# STB_SensorBoard.net
KiCad netlist of a schematic drawn in Altium Designer
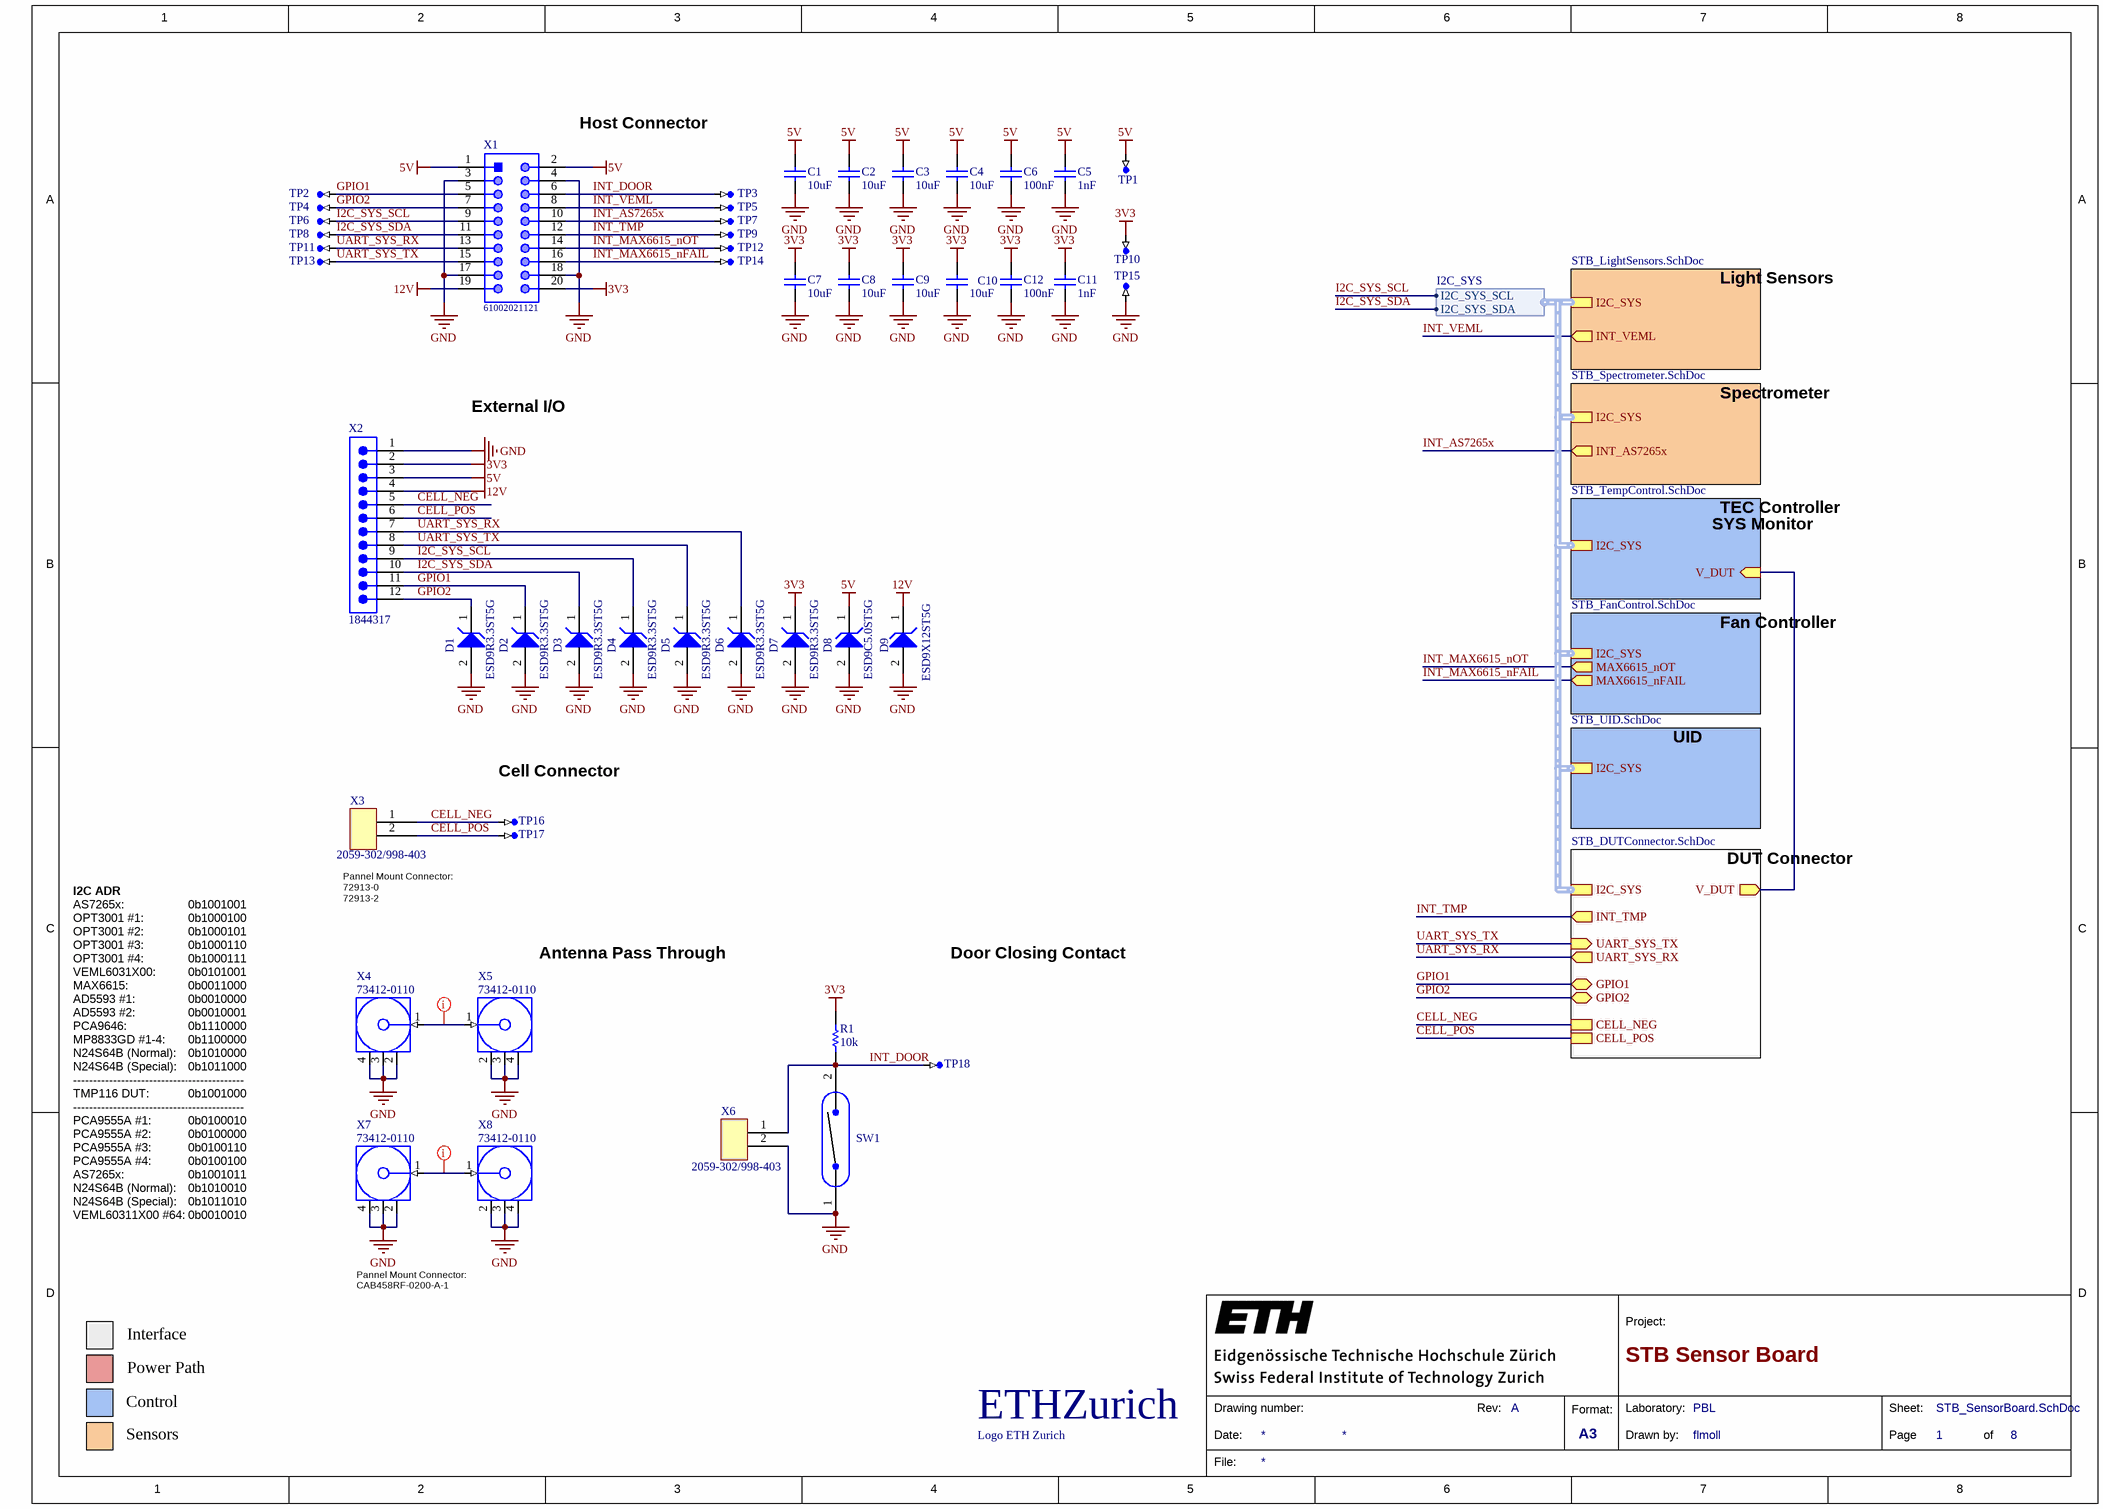
[diagram p0: STB_SensorBoard.SchDoc]

(export (version "E")
  (design (tool "Eeschema 10.0.6"))
  (components
    (comp (ref "A1")
      (value "Logo ETH Zurich")
      (footprint "eth-zurich_5mm")
      (libsource (lib "ETHZ Vault") (part "Logo ETH Zurich"))
    )
    (comp (ref "C1")
      (value "10uF")
      (footprint "CAPC0603(1608)100_L")
      (description "CAP 10uF 10V ±10% 0603 (1608 Metric) Thickness 1mm SMD")
      (fields (field (name "TOLERANCE") "Â±10%") (field (name "MANUFACTURER") "Samsung"))
      (libsource (lib "Altium Content Vault") (part "CMP-1035-02799-1"))
    )
    (comp (ref "C2")
      (value "10uF")
      (footprint "CAPC0603(1608)100_L")
      (description "CAP 10uF 10V ±10% 0603 (1608 Metric) Thickness 1mm SMD")
      (fields (field (name "TOLERANCE") "Â±10%") (field (name "MANUFACTURER") "Samsung"))
      (libsource (lib "Altium Content Vault") (part "CMP-1035-02799-1"))
    )
    (comp (ref "C3")
      (value "10uF")
      (footprint "CAPC0603(1608)100_L")
      (description "CAP 10uF 10V ±10% 0603 (1608 Metric) Thickness 1mm SMD")
      (fields (field (name "TOLERANCE") "Â±10%") (field (name "MANUFACTURER") "Samsung"))
      (libsource (lib "Altium Content Vault") (part "CMP-1035-02799-1"))
    )
    (comp (ref "C4")
      (value "10uF")
      (footprint "CAPC0603(1608)100_L")
      (description "CAP 10uF 10V ±10% 0603 (1608 Metric) Thickness 1mm SMD")
      (fields (field (name "TOLERANCE") "Â±10%") (field (name "MANUFACTURER") "Samsung"))
      (libsource (lib "Altium Content Vault") (part "CMP-1035-02799-1"))
    )
    (comp (ref "C5")
      (value "1nF")
      (footprint "CAPC1005X55X25ML5T10")
      (description "Chip Capacitor, 1 nF, +/- 10%, 50 V, -55 to 125 degC, 0402 (1005 Metric), RoHS, Tape and Reel")
      (fields (field (name "TOLERANCE") "10%") (field (name "MANUFACTURER") "Murata"))
      (libsource (lib "") (part "CAP-NP-2_1"))
    )
    (comp (ref "C6")
      (value "100nF")
      (footprint "CAPC1050X55X23LL05T13")
      (description "Chip Capacitor, 100 nF, +/- 10%, 16 V, -55 to 125 degC, 0402 (1005 Metric), RoHS, Tape and Reel")
      (fields
        (field (name "MANUFACTURER") "Samsung Electro-Mechanics")
        (field (name "MANUFACTURER PART NUMBER") "CL05B104KO5NNNC")
      )
      (libsource (lib "Altium Content Vault") (part "CAP-NP-2"))
    )
    (comp (ref "C7")
      (value "10uF")
      (footprint "CAPC0603(1608)100_L")
      (description "CAP 10uF 10V ±10% 0603 (1608 Metric) Thickness 1mm SMD")
      (fields (field (name "TOLERANCE") "Â±10%") (field (name "MANUFACTURER") "Samsung"))
      (libsource (lib "Altium Content Vault") (part "CMP-1035-02799-1"))
    )
    (comp (ref "C8")
      (value "10uF")
      (footprint "CAPC0603(1608)100_L")
      (description "CAP 10uF 10V ±10% 0603 (1608 Metric) Thickness 1mm SMD")
      (fields (field (name "TOLERANCE") "Â±10%") (field (name "MANUFACTURER") "Samsung"))
      (libsource (lib "Altium Content Vault") (part "CMP-1035-02799-1"))
    )
    (comp (ref "C9")
      (value "10uF")
      (footprint "CAPC0603(1608)100_L")
      (description "CAP 10uF 10V ±10% 0603 (1608 Metric) Thickness 1mm SMD")
      (fields (field (name "TOLERANCE") "Â±10%") (field (name "MANUFACTURER") "Samsung"))
      (libsource (lib "Altium Content Vault") (part "CMP-1035-02799-1"))
    )
    (comp (ref "C10")
      (value "10uF")
      (footprint "CAPC0603(1608)100_L")
      (description "CAP 10uF 10V ±10% 0603 (1608 Metric) Thickness 1mm SMD")
      (fields (field (name "TOLERANCE") "Â±10%") (field (name "MANUFACTURER") "Samsung"))
      (libsource (lib "Altium Content Vault") (part "CMP-1035-02799-1"))
    )
    (comp (ref "C11")
      (value "1nF")
      (footprint "CAPC1005X55X25ML5T10")
      (description "Chip Capacitor, 1 nF, +/- 10%, 50 V, -55 to 125 degC, 0402 (1005 Metric), RoHS, Tape and Reel")
      (fields (field (name "TOLERANCE") "10%") (field (name "MANUFACTURER") "Murata"))
      (libsource (lib "") (part "CAP-NP-2_1"))
    )
    (comp (ref "C12")
      (value "100nF")
      (footprint "CAPC1050X55X23LL05T13")
      (description "Chip Capacitor, 100 nF, +/- 10%, 16 V, -55 to 125 degC, 0402 (1005 Metric), RoHS, Tape and Reel")
      (fields
        (field (name "MANUFACTURER") "Samsung Electro-Mechanics")
        (field (name "MANUFACTURER PART NUMBER") "CL05B104KO5NNNC")
      )
      (libsource (lib "Altium Content Vault") (part "CAP-NP-2"))
    )
    (comp (ref "D1")
      (value "ESD9R3.3ST5G")
      (footprint "ONSC-SOD-923-2-514AB-01_V")
      (fields
        (field (name "MANUFACTURER") "On Semiconductor")
        (field (name "MANUFACTURER PART NUMBER") "SZESD9R3.3ST5G")
      )
      (libsource (lib "Altium Content Vault") (part "ONSC-K1A2-2_A"))
    )
    (comp (ref "D2")
      (value "ESD9R3.3ST5G")
      (footprint "ONSC-SOD-923-2-514AB-01_V")
      (fields
        (field (name "MANUFACTURER") "On Semiconductor")
        (field (name "MANUFACTURER PART NUMBER") "SZESD9R3.3ST5G")
      )
      (libsource (lib "Altium Content Vault") (part "ONSC-K1A2-2_A"))
    )
    (comp (ref "D3")
      (value "ESD9R3.3ST5G")
      (footprint "ONSC-SOD-923-2-514AB-01_V")
      (fields
        (field (name "MANUFACTURER") "On Semiconductor")
        (field (name "MANUFACTURER PART NUMBER") "SZESD9R3.3ST5G")
      )
      (libsource (lib "Altium Content Vault") (part "ONSC-K1A2-2_A"))
    )
    (comp (ref "D4")
      (value "ESD9R3.3ST5G")
      (footprint "ONSC-SOD-923-2-514AB-01_V")
      (fields
        (field (name "MANUFACTURER") "On Semiconductor")
        (field (name "MANUFACTURER PART NUMBER") "SZESD9R3.3ST5G")
      )
      (libsource (lib "Altium Content Vault") (part "ONSC-K1A2-2_A"))
    )
    (comp (ref "D5")
      (value "ESD9R3.3ST5G")
      (footprint "ONSC-SOD-923-2-514AB-01_V")
      (fields
        (field (name "MANUFACTURER") "On Semiconductor")
        (field (name "MANUFACTURER PART NUMBER") "SZESD9R3.3ST5G")
      )
      (libsource (lib "Altium Content Vault") (part "ONSC-K1A2-2_A"))
    )
    (comp (ref "D6")
      (value "ESD9R3.3ST5G")
      (footprint "ONSC-SOD-923-2-514AB-01_V")
      (fields
        (field (name "MANUFACTURER") "On Semiconductor")
        (field (name "MANUFACTURER PART NUMBER") "SZESD9R3.3ST5G")
      )
      (libsource (lib "Altium Content Vault") (part "ONSC-K1A2-2_A"))
    )
    (comp (ref "D7")
      (value "ESD9R3.3ST5G")
      (footprint "ONSC-SOD-923-2-514AB-01_V")
      (fields
        (field (name "MANUFACTURER") "On Semiconductor")
        (field (name "MANUFACTURER PART NUMBER") "SZESD9R3.3ST5G")
      )
      (libsource (lib "Altium Content Vault") (part "ONSC-K1A2-2_A"))
    )
    (comp (ref "D8")
      (value "ESD9C5.0ST5G")
      (footprint "ONSC-SOD-923-2-514AB-01_V")
      (fields (field (name "MANUFACTURER") "On Semiconductor"))
      (libsource (lib "Altium Content Vault") (part "ONSC-K1A2-2"))
    )
    (comp (ref "D9")
      (value "ESD9X12ST5G")
      (footprint "ONSC-SOD-923-2-514AA-01_V")
      (fields (field (name "MANUFACTURER") "On Semiconductor"))
      (libsource (lib "Altium Content Vault") (part "ONSC-K1A2-2"))
    )
    (comp (ref "R1")
      (value "10k")
      (footprint "RESC1005X40X25LL05T05")
      (description "Chip Resistor, 10 KOhm, +/- 1%, 0.1 W, -55 to 155 degC, 0402 (1005 Metric), RoHS, Tape and Reel")
      (fields (field (name "TOLERANCE") "1%") (field (name "MANUFACTURER") "Panasonic"))
      (libsource (lib "Altium Content Vault") (part "RES-2"))
    )
    (comp (ref "SW1")
      (value "MK17-B-2")
      (footprint "SMEL-MK17-B-2_V")
      (description "Molded Body Reed Switch, 100 V, 10 W, -40 to 130 degC, 2-Pin SMD, RoHS, Tape and Reel")
      (fields (field (name "MANUFACTURER") "Standex Meder"))
      (libsource (lib "Altium Content Vault") (part "SW-REED-2"))
    )
    (comp (ref "TP1")
      (value "testPoint_1mm")
      (footprint "TP-SM-C-100")
      (description "testPoint 1mm")
      (libsource (lib "STB_Schlib") (part "testPoint_1mm"))
    )
    (comp (ref "TP2")
      (value "testPoint_1mm")
      (footprint "TP-SM-C-100")
      (description "testPoint 1mm")
      (libsource (lib "STB_Schlib") (part "testPoint_1mm"))
    )
    (comp (ref "TP3")
      (value "testPoint_1mm")
      (footprint "TP-SM-C-100")
      (description "testPoint 1mm")
      (libsource (lib "STB_Schlib") (part "testPoint_1mm"))
    )
    (comp (ref "TP4")
      (value "testPoint_1mm")
      (footprint "TP-SM-C-100")
      (description "testPoint 1mm")
      (libsource (lib "STB_Schlib") (part "testPoint_1mm"))
    )
    (comp (ref "TP5")
      (value "testPoint_1mm")
      (footprint "TP-SM-C-100")
      (description "testPoint 1mm")
      (libsource (lib "STB_Schlib") (part "testPoint_1mm"))
    )
    (comp (ref "TP6")
      (value "testPoint_1mm")
      (footprint "TP-SM-C-100")
      (description "testPoint 1mm")
      (libsource (lib "STB_Schlib") (part "testPoint_1mm"))
    )
    (comp (ref "TP7")
      (value "testPoint_1mm")
      (footprint "TP-SM-C-100")
      (description "testPoint 1mm")
      (libsource (lib "STB_Schlib") (part "testPoint_1mm"))
    )
    (comp (ref "TP8")
      (value "testPoint_1mm")
      (footprint "TP-SM-C-100")
      (description "testPoint 1mm")
      (libsource (lib "STB_Schlib") (part "testPoint_1mm"))
    )
    (comp (ref "TP9")
      (value "testPoint_1mm")
      (footprint "TP-SM-C-100")
      (description "testPoint 1mm")
      (libsource (lib "STB_Schlib") (part "testPoint_1mm"))
    )
    (comp (ref "TP10")
      (value "testPoint_1mm")
      (footprint "TP-SM-C-100")
      (description "testPoint 1mm")
      (libsource (lib "STB_Schlib") (part "testPoint_1mm"))
    )
    (comp (ref "TP11")
      (value "testPoint_1mm")
      (footprint "TP-SM-C-100")
      (description "testPoint 1mm")
      (libsource (lib "STB_Schlib") (part "testPoint_1mm"))
    )
    (comp (ref "TP12")
      (value "testPoint_1mm")
      (footprint "TP-SM-C-100")
      (description "testPoint 1mm")
      (libsource (lib "STB_Schlib") (part "testPoint_1mm"))
    )
    (comp (ref "TP13")
      (value "testPoint_1mm")
      (footprint "TP-SM-C-100")
      (description "testPoint 1mm")
      (libsource (lib "STB_Schlib") (part "testPoint_1mm"))
    )
    (comp (ref "TP14")
      (value "testPoint_1mm")
      (footprint "TP-SM-C-100")
      (description "testPoint 1mm")
      (libsource (lib "STB_Schlib") (part "testPoint_1mm"))
    )
    (comp (ref "TP15")
      (value "testPoint_1mm")
      (footprint "TP-SM-C-100")
      (description "testPoint 1mm")
      (libsource (lib "STB_Schlib") (part "testPoint_1mm"))
    )
    (comp (ref "TP16")
      (value "testPoint_1mm")
      (footprint "TP-SM-C-100")
      (description "testPoint 1mm")
      (libsource (lib "STB_Schlib") (part "testPoint_1mm"))
    )
    (comp (ref "TP17")
      (value "testPoint_1mm")
      (footprint "TP-SM-C-100")
      (description "testPoint 1mm")
      (libsource (lib "STB_Schlib") (part "testPoint_1mm"))
    )
    (comp (ref "TP18")
      (value "testPoint_1mm")
      (footprint "TP-SM-C-100")
      (description "testPoint 1mm")
      (libsource (lib "STB_Schlib") (part "testPoint_1mm"))
    )
    (comp (ref "X1")
      (value "61002021121")
      (footprint "61002021121")
      (description "SMT Vertical Pin Header WR-PHD, Pitch 2.54 mm, Dual Row, 20 pins")
      (fields (field (name "MANUFACTURER") "Wurth Elektronik") (field (name "PUBLISHER") "WurthElektronik"))
      (libsource (lib "Altium Content Vault") (part "WE-CN-2P-M-R20"))
    )
    (comp (ref "X2")
      (value "1844317")
      (footprint "1844317")
      (fields (field (name "MANUFACTURER") "Phoenix Contact"))
      (libsource (lib "ETHZ Vault") (part "CON-1x12-Male"))
    )
    (comp (ref "X3")
      (value "2059-302/998-403")
      (footprint "2059-302/998-403")
      (description "Barrier Strip Terminal Block, 3A, 0.34mm2, 1 Row(s), 1 Deck(s)")
      (fields (field (name "MANUFACTURER") "WAGO") (field (name "SAFETY APPROVAL") "UL"))
      (libsource (lib "STB_Schlib") (part "2059-302/998-403"))
    )
    (comp (ref "X4")
      (value "73412-0110")
      (footprint "MOLX-73412-0110_V")
      (description "MCRF, PCB Vertical Jack Receptacle, 50 Ohm, 4-Pin SMD, RoHS, Tape and Reel")
      (fields (field (name "MANUFACTURER") "Molex"))
      (libsource (lib "Altium Content Vault") (part "MOLX-73412-0110"))
    )
    (comp (ref "X5")
      (value "73412-0110")
      (footprint "MOLX-73412-0110_V")
      (description "MCRF, PCB Vertical Jack Receptacle, 50 Ohm, 4-Pin SMD, RoHS, Tape and Reel")
      (fields (field (name "MANUFACTURER") "Molex"))
      (libsource (lib "Altium Content Vault") (part "MOLX-73412-0110"))
    )
    (comp (ref "X6")
      (value "2059-302/998-403")
      (footprint "2059-302/998-403")
      (description "Barrier Strip Terminal Block, 3A, 0.34mm2, 1 Row(s), 1 Deck(s)")
      (fields (field (name "MANUFACTURER") "WAGO") (field (name "SAFETY APPROVAL") "UL"))
      (libsource (lib "STB_Schlib") (part "2059-302/998-403"))
    )
    (comp (ref "X7")
      (value "73412-0110")
      (footprint "MOLX-73412-0110_V")
      (description "MCRF, PCB Vertical Jack Receptacle, 50 Ohm, 4-Pin SMD, RoHS, Tape and Reel")
      (fields (field (name "MANUFACTURER") "Molex"))
      (libsource (lib "Altium Content Vault") (part "MOLX-73412-0110"))
    )
    (comp (ref "X8")
      (value "73412-0110")
      (footprint "MOLX-73412-0110_V")
      (description "MCRF, PCB Vertical Jack Receptacle, 50 Ohm, 4-Pin SMD, RoHS, Tape and Reel")
      (fields (field (name "MANUFACTURER") "Molex"))
      (libsource (lib "Altium Content Vault") (part "MOLX-73412-0110"))
    )
  )
  (nets
    (net (code "2") (name "/CELL_NEG") (class "Default")
      (node (ref "TP16") (pin "TP") (pinfunction "TP_TP") (pintype "input"))
      (node (ref "X2") (pin "5") (pinfunction "5_5") (pintype "passive"))
      (node (ref "X3") (pin "1") (pintype "passive"))
    )
    (net (code "3") (name "/CELL_POS") (class "Default")
      (node (ref "TP17") (pin "TP") (pinfunction "TP_TP") (pintype "input"))
      (node (ref "X2") (pin "6") (pinfunction "6_6") (pintype "passive"))
      (node (ref "X3") (pin "2") (pintype "passive"))
    )
    (net (code "4") (name "/GPIO1") (class "Default")
      (node (ref "D2") (pin "1") (pinfunction "K_1") (pintype "passive"))
      (node (ref "TP2") (pin "TP") (pinfunction "TP_TP") (pintype "input"))
      (node (ref "X1") (pin "5") (pinfunction "5_5") (pintype "passive"))
      (node (ref "X2") (pin "11") (pinfunction "11_11") (pintype "passive"))
    )
    (net (code "5") (name "/GPIO2") (class "Default")
      (node (ref "D1") (pin "1") (pinfunction "K_1") (pintype "passive"))
      (node (ref "TP4") (pin "TP") (pinfunction "TP_TP") (pintype "input"))
      (node (ref "X1") (pin "7") (pinfunction "7_7") (pintype "passive"))
      (node (ref "X2") (pin "12") (pinfunction "12_12") (pintype "passive"))
    )
    (net (code "6") (name "/I2C_SYS_SCL") (class "Default")
      (node (ref "D4") (pin "1") (pinfunction "K_1") (pintype "passive"))
      (node (ref "TP6") (pin "TP") (pinfunction "TP_TP") (pintype "input"))
      (node (ref "X1") (pin "9") (pinfunction "9_9") (pintype "passive"))
      (node (ref "X2") (pin "9") (pinfunction "9_9") (pintype "passive"))
    )
    (net (code "7") (name "/I2C_SYS_SDA") (class "Default")
      (node (ref "D3") (pin "1") (pinfunction "K_1") (pintype "passive"))
      (node (ref "TP8") (pin "TP") (pinfunction "TP_TP") (pintype "input"))
      (node (ref "X1") (pin "11") (pinfunction "11_11") (pintype "passive"))
      (node (ref "X2") (pin "10") (pinfunction "10_10") (pintype "passive"))
    )
    (net (code "8") (name "/INT_AS7265x") (class "Default")
      (node (ref "TP7") (pin "TP") (pinfunction "TP_TP") (pintype "input"))
      (node (ref "X1") (pin "10") (pinfunction "10_10") (pintype "passive"))
    )
    (net (code "9") (name "/INT_DOOR") (class "Default")
      (node (ref "R1") (pin "1") (pinfunction "1_1") (pintype "passive"))
      (node (ref "SW1") (pin "2") (pinfunction "2_2") (pintype "passive"))
      (node (ref "TP18") (pin "TP") (pinfunction "TP_TP") (pintype "input"))
      (node (ref "TP3") (pin "TP") (pinfunction "TP_TP") (pintype "input"))
      (node (ref "X1") (pin "6") (pinfunction "6_6") (pintype "passive"))
      (node (ref "X6") (pin "1") (pintype "passive"))
    )
    (net (code "10") (name "/INT_MAX6615_nFAIL") (class "Default")
      (node (ref "TP14") (pin "TP") (pinfunction "TP_TP") (pintype "input"))
      (node (ref "X1") (pin "16") (pinfunction "16_16") (pintype "passive"))
    )
    (net (code "11") (name "/INT_MAX6615_nOT") (class "Default")
      (node (ref "TP12") (pin "TP") (pinfunction "TP_TP") (pintype "input"))
      (node (ref "X1") (pin "14") (pinfunction "14_14") (pintype "passive"))
    )
    (net (code "12") (name "/INT_TMP") (class "Default")
      (node (ref "TP9") (pin "TP") (pinfunction "TP_TP") (pintype "input"))
      (node (ref "X1") (pin "12") (pinfunction "12_12") (pintype "passive"))
    )
    (net (code "13") (name "/INT_VEML") (class "Default")
      (node (ref "TP5") (pin "TP") (pinfunction "TP_TP") (pintype "input"))
      (node (ref "X1") (pin "8") (pinfunction "8_8") (pintype "passive"))
    )
    (net (code "14") (name "/UART_SYS_RX") (class "Default")
      (node (ref "D6") (pin "1") (pinfunction "K_1") (pintype "passive"))
      (node (ref "TP11") (pin "TP") (pinfunction "TP_TP") (pintype "input"))
      (node (ref "X1") (pin "13") (pinfunction "13_13") (pintype "passive"))
      (node (ref "X2") (pin "7") (pinfunction "7_7") (pintype "passive"))
    )
    (net (code "15") (name "/UART_SYS_TX") (class "Default")
      (node (ref "D5") (pin "1") (pinfunction "K_1") (pintype "passive"))
      (node (ref "TP13") (pin "TP") (pinfunction "TP_TP") (pintype "input"))
      (node (ref "X1") (pin "15") (pinfunction "15_15") (pintype "passive"))
      (node (ref "X2") (pin "8") (pinfunction "8_8") (pintype "passive"))
    )
    (net (code "18") (name "3V3") (class "Default")
      (node (ref "C10") (pin "2") (pinfunction "2_2") (pintype "passive"))
      (node (ref "C11") (pin "2") (pinfunction "2_2") (pintype "passive"))
      (node (ref "C12") (pin "2") (pinfunction "2_2") (pintype "passive"))
      (node (ref "C7") (pin "2") (pinfunction "2_2") (pintype "passive"))
      (node (ref "C8") (pin "2") (pinfunction "2_2") (pintype "passive"))
      (node (ref "C9") (pin "2") (pinfunction "2_2") (pintype "passive"))
      (node (ref "D7") (pin "1") (pinfunction "K_1") (pintype "passive"))
      (node (ref "R1") (pin "2") (pinfunction "2_2") (pintype "passive"))
      (node (ref "TP10") (pin "TP") (pinfunction "TP_TP") (pintype "input"))
      (node (ref "X1") (pin "20") (pinfunction "20_20") (pintype "passive"))
      (node (ref "X2") (pin "2") (pinfunction "2_2") (pintype "passive"))
    )
    (net (code "19") (name "5V") (class "Default")
      (node (ref "C1") (pin "2") (pinfunction "2_2") (pintype "passive"))
      (node (ref "C2") (pin "2") (pinfunction "2_2") (pintype "passive"))
      (node (ref "C3") (pin "2") (pinfunction "2_2") (pintype "passive"))
      (node (ref "C4") (pin "2") (pinfunction "2_2") (pintype "passive"))
      (node (ref "C5") (pin "2") (pinfunction "2_2") (pintype "passive"))
      (node (ref "C6") (pin "2") (pinfunction "2_2") (pintype "passive"))
      (node (ref "D8") (pin "1") (pinfunction "K_1") (pintype "passive"))
      (node (ref "TP1") (pin "TP") (pinfunction "TP_TP") (pintype "input"))
      (node (ref "X1") (pin "1") (pinfunction "1_1") (pintype "passive"))
      (node (ref "X1") (pin "2") (pinfunction "2_2") (pintype "passive"))
      (node (ref "X2") (pin "3") (pinfunction "3_3") (pintype "passive"))
    )
    (net (code "20") (name "12V") (class "Default")
      (node (ref "D9") (pin "1") (pinfunction "K_1") (pintype "passive"))
      (node (ref "X1") (pin "19") (pinfunction "19_19") (pintype "passive"))
      (node (ref "X2") (pin "4") (pinfunction "4_4") (pintype "passive"))
    )
    (net (code "21") (name "GND") (class "Default")
      (node (ref "C1") (pin "1") (pinfunction "1_1") (pintype "passive"))
      (node (ref "C10") (pin "1") (pinfunction "1_1") (pintype "passive"))
      (node (ref "C11") (pin "1") (pinfunction "1_1") (pintype "passive"))
      (node (ref "C12") (pin "1") (pinfunction "1_1") (pintype "passive"))
      (node (ref "C2") (pin "1") (pinfunction "1_1") (pintype "passive"))
      (node (ref "C3") (pin "1") (pinfunction "1_1") (pintype "passive"))
      (node (ref "C4") (pin "1") (pinfunction "1_1") (pintype "passive"))
      (node (ref "C5") (pin "1") (pinfunction "1_1") (pintype "passive"))
      (node (ref "C6") (pin "1") (pinfunction "1_1") (pintype "passive"))
      (node (ref "C7") (pin "1") (pinfunction "1_1") (pintype "passive"))
      (node (ref "C8") (pin "1") (pinfunction "1_1") (pintype "passive"))
      (node (ref "C9") (pin "1") (pinfunction "1_1") (pintype "passive"))
      (node (ref "D1") (pin "2") (pinfunction "A_2") (pintype "passive"))
      (node (ref "D2") (pin "2") (pinfunction "A_2") (pintype "passive"))
      (node (ref "D3") (pin "2") (pinfunction "A_2") (pintype "passive"))
      (node (ref "D4") (pin "2") (pinfunction "A_2") (pintype "passive"))
      (node (ref "D5") (pin "2") (pinfunction "A_2") (pintype "passive"))
      (node (ref "D6") (pin "2") (pinfunction "A_2") (pintype "passive"))
      (node (ref "D7") (pin "2") (pinfunction "A_2") (pintype "passive"))
      (node (ref "D8") (pin "2") (pinfunction "A_2") (pintype "passive"))
      (node (ref "D9") (pin "2") (pinfunction "A_2") (pintype "passive"))
      (node (ref "SW1") (pin "1") (pinfunction "1_1") (pintype "passive"))
      (node (ref "TP15") (pin "TP") (pinfunction "TP_TP") (pintype "input"))
      (node (ref "X1") (pin "17") (pinfunction "17_17") (pintype "passive"))
      (node (ref "X1") (pin "18") (pinfunction "18_18") (pintype "passive"))
      (node (ref "X1") (pin "3") (pinfunction "3_3") (pintype "passive"))
      (node (ref "X1") (pin "4") (pinfunction "4_4") (pintype "passive"))
      (node (ref "X2") (pin "1") (pinfunction "1_1") (pintype "passive"))
      (node (ref "X4") (pin "2") (pinfunction "GND_2") (pintype "power_in"))
      (node (ref "X4") (pin "3") (pinfunction "GND_3") (pintype "power_in"))
      (node (ref "X4") (pin "4") (pinfunction "GND_4") (pintype "power_in"))
      (node (ref "X5") (pin "2") (pinfunction "GND_2") (pintype "power_in"))
      (node (ref "X5") (pin "3") (pinfunction "GND_3") (pintype "power_in"))
      (node (ref "X5") (pin "4") (pinfunction "GND_4") (pintype "power_in"))
      (node (ref "X6") (pin "2") (pintype "passive"))
      (node (ref "X7") (pin "2") (pinfunction "GND_2") (pintype "power_in"))
      (node (ref "X7") (pin "3") (pinfunction "GND_3") (pintype "power_in"))
      (node (ref "X7") (pin "4") (pinfunction "GND_4") (pintype "power_in"))
      (node (ref "X8") (pin "2") (pinfunction "GND_2") (pintype "power_in"))
      (node (ref "X8") (pin "3") (pinfunction "GND_3") (pintype "power_in"))
      (node (ref "X8") (pin "4") (pinfunction "GND_4") (pintype "power_in"))
    )
    (net (code "22") (name "Net-(X4-SIGNAL)") (class "Default")
      (node (ref "X4") (pin "1") (pinfunction "SIGNAL_1") (pintype "input"))
      (node (ref "X5") (pin "1") (pinfunction "SIGNAL_1") (pintype "input"))
    )
    (net (code "23") (name "Net-(X7-SIGNAL)") (class "Default")
      (node (ref "X7") (pin "1") (pinfunction "SIGNAL_1") (pintype "input"))
      (node (ref "X8") (pin "1") (pinfunction "SIGNAL_1") (pintype "input"))
    )
  )
)
